# Buck_Converter_Sch.net
KiCad netlist of a schematic drawn in Altium Designer
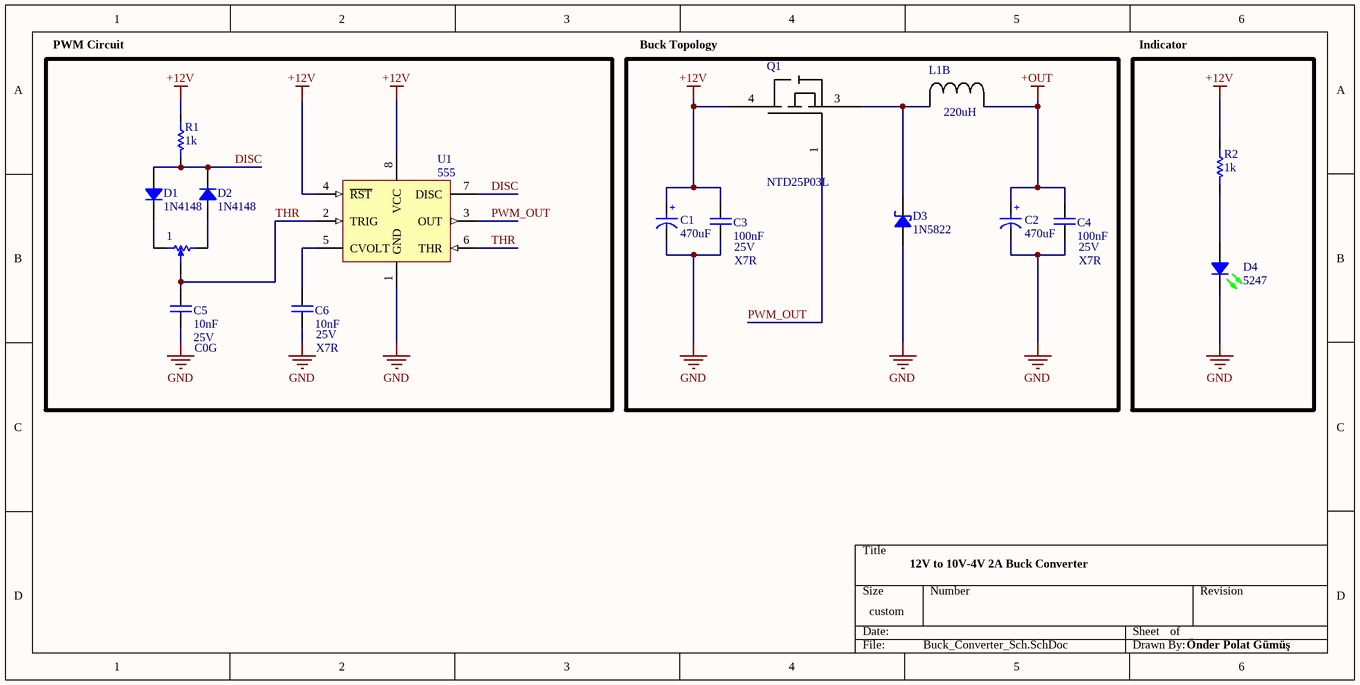
[diagram p0: Buck_Converter_Sch.SchDoc]

(export (version "E")
  (design (tool "Eeschema 10.0.6"))
  (components
    (comp (ref "1")
      (value "Value?")
      (footprint "POT4MM-Small Pot")
      (description "Square Trimming Potentiometer")
      (fields (field (name "VALIDATION") "NT"))
      (libsource (lib "aKaReZa") (part "Res_Pot_SM"))
    )
    (comp (ref "C1")
      (value "470u'F, 25'V")
      (footprint "Cap 03")
      (description "Electrolit Capacitor")
      (fields (field (name "INFLOW") "470uF") (field (name "VALIDATION") "NT"))
      (libsource (lib "aKaReZa") (part "Cap_Elec_470u_25"))
    )
    (comp (ref "C2")
      (value "470u'F, 25'V")
      (footprint "Cap 03")
      (description "Electrolit Capacitor")
      (fields (field (name "INFLOW") "470uF") (field (name "VALIDATION") "NT"))
      (libsource (lib "aKaReZa") (part "Cap_Elec_470u_25"))
    )
    (comp (ref "C3")
      (value "100nF")
      (footprint "CAP 1206/3216")
      (description "Bipolar ceramic capacitor SMD")
      (fields (field (name "RATING") "25V") (field (name "VALIDATION") "Valid"))
      (libsource (lib "aKaReZa") (part "Cap_Multi_SMD"))
    )
    (comp (ref "C4")
      (value "100nF")
      (footprint "CAP 1206/3216")
      (description "Bipolar ceramic capacitor SMD")
      (fields (field (name "RATING") "25V") (field (name "VALIDATION") "Valid"))
      (libsource (lib "aKaReZa") (part "Cap_Multi_SMD"))
    )
    (comp (ref "C5")
      (value "10nF")
      (footprint "CAP 1206/3216")
      (description "Bipolar ceramic capacitor SMD")
      (fields (field (name "RATING") "25V") (field (name "VALIDATION") "Valid"))
      (libsource (lib "aKaReZa") (part "Cap_Multi_SMD"))
    )
    (comp (ref "C6")
      (value "10nF")
      (footprint "CAP 1206/3216")
      (description "Bipolar ceramic capacitor SMD")
      (fields (field (name "RATING") "25V") (field (name "VALIDATION") "Valid"))
      (libsource (lib "aKaReZa") (part "Cap_Multi_SMD"))
    )
    (comp (ref "D1")
      (value "1N4148")
      (footprint "DO-35")
      (description "High Conductance Fast Diode")
      (fields (field (name "INFLOW") "1N4148") (field (name "VALIDATION") "NT"))
      (libsource (lib "aKaReZa") (part "Semi_Diod_STD_1N4148"))
    )
    (comp (ref "D2")
      (value "1N4148")
      (footprint "DO-35")
      (description "High Conductance Fast Diode")
      (fields (field (name "INFLOW") "1N4148") (field (name "VALIDATION") "NT"))
      (libsource (lib "aKaReZa") (part "Semi_Diod_STD_1N4148"))
    )
    (comp (ref "D3")
      (value "1N5822")
      (footprint "BYW98")
      (description "Schottky Rectifiers")
      (fields (field (name "INFLOW") "1N5822") (field (name "VALIDATION") "NT"))
      (libsource (lib "aKaReZa") (part "Semi_Diod_Sch_1N5822"))
    )
    (comp (ref "D4")
      (value "Green, 1206")
      (footprint "LED 1206/3216 GREEN")
      (description "LED")
      (fields (field (name "INFLOW") "5247") (field (name "VALIDATION") "Valid"))
      (libsource (lib "aKaReZa") (part "Semi_LED_Green_1206"))
    )
    (comp (ref "L1")
      (value "220uH")
      (footprint "12x12x10mm_Inductor")
      (libsource (lib "Inductor_Library_12x12x10") (part "12x12x10mm Inductor"))
    )
    (comp (ref "Q1")
      (value "NTD25P03L")
      (footprint "TO229P990X238-3N")
      (libsource (lib "NTD25P03LT4G") (part "NTD25P03L"))
    )
    (comp (ref "R1")
      (value "1k")
      (footprint "RES 1206 (3216X08L)")
      (description "Resistor")
      (fields (field (name "VALIDATION") "Valid"))
      (libsource (lib "aKaReZa") (part "Res_SMD"))
    )
    (comp (ref "R2")
      (value "1k")
      (footprint "RES 1206 (3216X08L)")
      (description "Resistor")
      (fields (field (name "VALIDATION") "Valid"))
      (libsource (lib "aKaReZa") (part "Res_SMD"))
    )
    (comp (ref "U1")
      (value "NE555")
      (footprint "SO8_narrow_m")
      (description "Astable or monostable operation timer")
      (fields (field (name "INFLOW") "555") (field (name "VALIDATION") "Valid"))
      (libsource (lib "aKaReZa") (part "IC_Timer_NE555_SMD"))
    )
  )
  (nets
    (net (code "1") (name "+12V") (class "Default")
      (node (ref "C1") (pin "1") (pinfunction "+_1") (pintype "passive"))
      (node (ref "C3") (pin "1") (pinfunction "1_1") (pintype "passive"))
      (node (ref "Q1") (pin "4") (pinfunction "2_4") (pintype "passive"))
      (node (ref "R1") (pin "1") (pinfunction "1_1") (pintype "passive"))
      (node (ref "R2") (pin "1") (pinfunction "1_1") (pintype "passive"))
      (node (ref "U1") (pin "4") (pinfunction "~{RST}_4") (pintype "input"))
      (node (ref "U1") (pin "8") (pinfunction "VCC_8") (pintype "power_in"))
    )
    (net (code "2") (name "+OUT") (class "Default")
      (node (ref "C2") (pin "1") (pinfunction "+_1") (pintype "passive"))
      (node (ref "C4") (pin "1") (pinfunction "1_1") (pintype "passive"))
      (node (ref "L1") (pin "1") (pinfunction "1_1") (pintype "passive"))
    )
    (net (code "3") (name "/DISC") (class "Default")
      (node (ref "D1") (pin "1") (pinfunction "1_1") (pintype "passive"))
      (node (ref "D2") (pin "2") (pinfunction "2_2") (pintype "passive"))
      (node (ref "R1") (pin "2") (pinfunction "2_2") (pintype "passive"))
      (node (ref "U1") (pin "7") (pinfunction "DISC_7") (pintype "open_collector"))
    )
    (net (code "4") (name "/PWM_OUT") (class "Default")
      (node (ref "Q1") (pin "1") (pinfunction "2_1") (pintype "passive"))
      (node (ref "U1") (pin "3") (pinfunction "OUT_3") (pintype "output"))
    )
    (net (code "5") (name "/THR") (class "Default")
      (node (ref "1") (pin "W") (pinfunction "W_W") (pintype "passive"))
      (node (ref "C5") (pin "1") (pinfunction "1_1") (pintype "passive"))
      (node (ref "U1") (pin "2") (pinfunction "TRIG_2") (pintype "input"))
      (node (ref "U1") (pin "6") (pinfunction "THR_6") (pintype "input"))
    )
    (net (code "6") (name "GND") (class "Default")
      (node (ref "C1") (pin "2") (pinfunction "-_2") (pintype "passive"))
      (node (ref "C2") (pin "2") (pinfunction "-_2") (pintype "passive"))
      (node (ref "C3") (pin "2") (pinfunction "2_2") (pintype "passive"))
      (node (ref "C4") (pin "2") (pinfunction "2_2") (pintype "passive"))
      (node (ref "C5") (pin "2") (pinfunction "2_2") (pintype "passive"))
      (node (ref "C6") (pin "2") (pinfunction "2_2") (pintype "passive"))
      (node (ref "D3") (pin "1") (pinfunction "1_1") (pintype "passive"))
      (node (ref "D4") (pin "2") (pinfunction "2_2") (pintype "passive"))
      (node (ref "U1") (pin "1") (pinfunction "GND_1") (pintype "power_in"))
    )
    (net (code "7") (name "Net-(1-+)") (class "Default")
      (node (ref "1") (pin "CW") (pinfunction "+_CW") (pintype "passive"))
      (node (ref "D1") (pin "2") (pinfunction "2_2") (pintype "passive"))
    )
    (net (code "8") (name "Net-(1--)") (class "Default")
      (node (ref "1") (pin "CCW") (pinfunction "-_CCW") (pintype "passive"))
      (node (ref "D2") (pin "1") (pinfunction "1_1") (pintype "passive"))
    )
    (net (code "9") (name "Net-(D4-Pad1)") (class "Default")
      (node (ref "D4") (pin "1") (pinfunction "1_1") (pintype "passive"))
      (node (ref "R2") (pin "2") (pinfunction "2_2") (pintype "passive"))
    )
    (net (code "10") (name "Net-(Q1-1)") (class "Default")
      (node (ref "D3") (pin "2") (pinfunction "2_2") (pintype "passive"))
      (node (ref "L1") (pin "0") (pinfunction "0_0") (pintype "passive"))
      (node (ref "Q1") (pin "3") (pinfunction "1_3") (pintype "passive"))
    )
    (net (code "11") (name "Net-(U1-CVOLT)") (class "Default")
      (node (ref "C6") (pin "1") (pinfunction "1_1") (pintype "passive"))
      (node (ref "U1") (pin "5") (pinfunction "CVOLT_5") (pintype "passive"))
    )
  )
)
